# ProPrj_2026_05_15_drone_2026-05-23.net
KiCad netlist of a schematic drawn in EasyEDA Pro
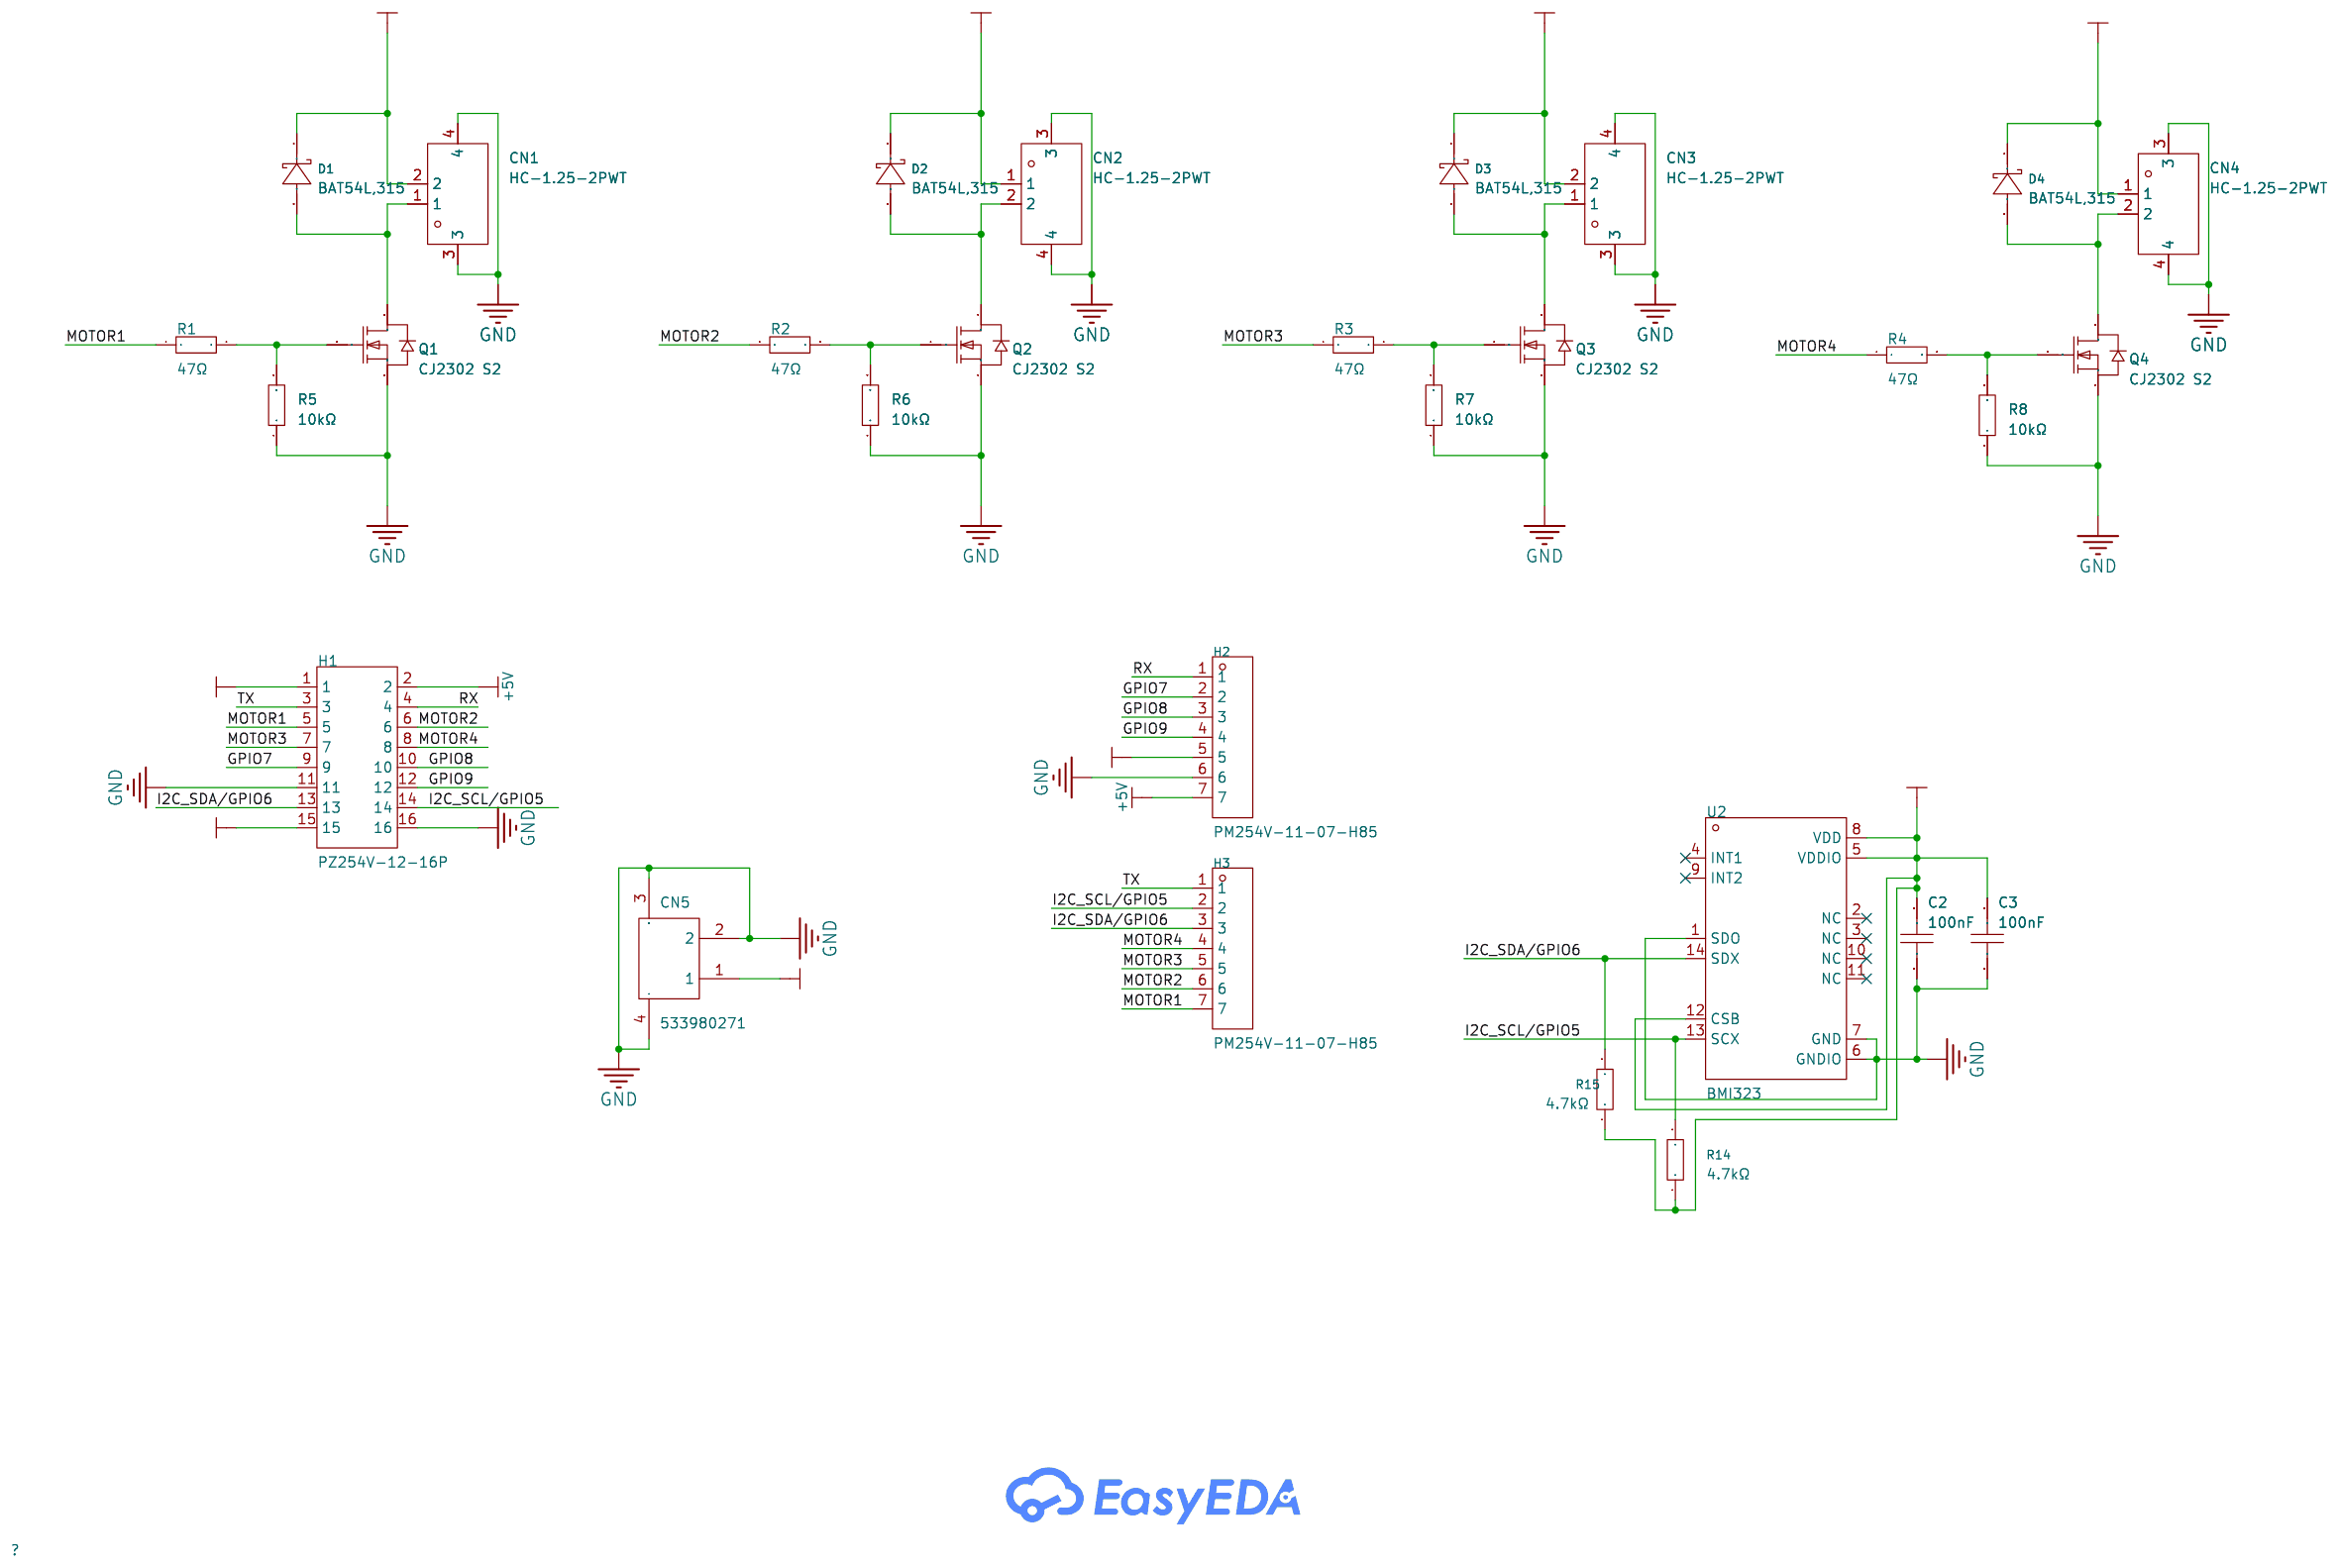
[diagram p0: schematic sheet]

(export (version "E")
  (design (tool "Eeschema 10.0.6"))
  (components
    (comp (ref "C2")
      (value "100nF")
      (footprint "easyedapro:C0402")
      (fields
        (field (name "Manufacturer Part") "CL05B104KO5NNNC")
        (field (name "Manufacturer") "SAMSUNG(三星)")
      )
      (libsource (lib "easyedapro") (part "CL05B104KO5NNNC"))
    )
    (comp (ref "C3")
      (value "100nF")
      (footprint "easyedapro:C0402")
      (fields
        (field (name "Manufacturer Part") "CL05B104KO5NNNC")
        (field (name "Manufacturer") "SAMSUNG(三星)")
      )
      (libsource (lib "easyedapro") (part "CL05B104KO5NNNC"))
    )
    (comp (ref "CN1")
      (value "HC-1.25-2PWT")
      (footprint "easyedapro:CONN-SMD_2P-P1.25-HC-1.25-2PWT")
      (fields (field (name "Manufacturer") "HCTL(华灿天禄)"))
      (libsource (lib "easyedapro") (part "HC-1.25-2PWT"))
    )
    (comp (ref "CN2")
      (value "HC-1.25-2PWT")
      (footprint "easyedapro:CONN-SMD_2P-P1.25-HC-1.25-2PWT")
      (fields (field (name "Manufacturer") "HCTL(华灿天禄)"))
      (libsource (lib "easyedapro") (part "HC-1.25-2PWT"))
    )
    (comp (ref "CN3")
      (value "HC-1.25-2PWT")
      (footprint "easyedapro:CONN-SMD_2P-P1.25-HC-1.25-2PWT")
      (fields (field (name "Manufacturer") "HCTL(华灿天禄)"))
      (libsource (lib "easyedapro") (part "HC-1.25-2PWT"))
    )
    (comp (ref "CN4")
      (value "HC-1.25-2PWT")
      (footprint "easyedapro:CONN-SMD_2P-P1.25-HC-1.25-2PWT")
      (fields (field (name "Manufacturer") "HCTL(华灿天禄)"))
      (libsource (lib "easyedapro") (part "HC-1.25-2PWT"))
    )
    (comp (ref "CN5")
      (value "533980271")
      (footprint "easyedapro:CONN-SMD_2P-P1.25_053398-0X71")
      (fields (field (name "Manufacturer") "MOLEX"))
      (libsource (lib "easyedapro") (part "0533980271"))
    )
    (comp (ref "D1")
      (value "BAT54L,315")
      (footprint "easyedapro:DFN1006-2L-RD")
      (fields (field (name "Manufacturer") "Nexperia(安世)"))
      (libsource (lib "easyedapro") (part "BAT54L,315"))
    )
    (comp (ref "D2")
      (value "BAT54L,315")
      (footprint "easyedapro:DFN1006-2L-RD")
      (fields (field (name "Manufacturer") "Nexperia(安世)"))
      (libsource (lib "easyedapro") (part "BAT54L,315"))
    )
    (comp (ref "D3")
      (value "BAT54L,315")
      (footprint "easyedapro:DFN1006-2L-RD")
      (fields (field (name "Manufacturer") "Nexperia(安世)"))
      (libsource (lib "easyedapro") (part "BAT54L,315"))
    )
    (comp (ref "D4")
      (value "BAT54L,315")
      (footprint "easyedapro:DFN1006-2L-RD")
      (fields (field (name "Manufacturer") "Nexperia(安世)"))
      (libsource (lib "easyedapro") (part "BAT54L,315"))
    )
    (comp (ref "H1")
      (value "PZ254V-12-16P")
      (footprint "easyedapro:HDR-TH_16P-P2.54-V-M-R2-C8-S2.54")
      (fields (field (name "Manufacturer") "XFCN(兴飞)"))
      (libsource (lib "easyedapro") (part "PZ254V-12-16P"))
    )
    (comp (ref "H2")
      (value "PM254V-11-07-H85")
      (footprint "easyedapro:HDR-TH_7P-P2.54-V-F")
      (fields (field (name "Manufacturer") "XFCN(兴飞)"))
      (libsource (lib "easyedapro") (part "PM254V-11-07-H85"))
    )
    (comp (ref "H3")
      (value "PM254V-11-07-H85")
      (footprint "easyedapro:HDR-TH_7P-P2.54-V-F")
      (fields (field (name "Manufacturer") "XFCN(兴飞)"))
      (libsource (lib "easyedapro") (part "PM254V-11-07-H85"))
    )
    (comp (ref "Q1")
      (value "CJ2302 S2")
      (footprint "easyedapro:SOT-23-3_L3.0-W1.7-P0.95-LS2.9-BR")
      (fields (field (name "Manufacturer") "CJ(江苏长电/长晶)"))
      (libsource (lib "easyedapro") (part "CJ2302 S2"))
    )
    (comp (ref "Q2")
      (value "CJ2302 S2")
      (footprint "easyedapro:SOT-23-3_L3.0-W1.7-P0.95-LS2.9-BR")
      (fields (field (name "Manufacturer") "CJ(江苏长电/长晶)"))
      (libsource (lib "easyedapro") (part "CJ2302 S2"))
    )
    (comp (ref "Q3")
      (value "CJ2302 S2")
      (footprint "easyedapro:SOT-23-3_L3.0-W1.7-P0.95-LS2.9-BR")
      (fields (field (name "Manufacturer") "CJ(江苏长电/长晶)"))
      (libsource (lib "easyedapro") (part "CJ2302 S2"))
    )
    (comp (ref "Q4")
      (value "CJ2302 S2")
      (footprint "easyedapro:SOT-23-3_L3.0-W1.7-P0.95-LS2.9-BR")
      (fields (field (name "Manufacturer") "CJ(江苏长电/长晶)"))
      (libsource (lib "easyedapro") (part "CJ2302 S2"))
    )
    (comp (ref "R1")
      (value "47Ω")
      (footprint "easyedapro:R0402")
      (fields (field (name "Manufacturer Part") "RC0402FR-0747RL") (field (name "Manufacturer") "YAGEO(国巨)"))
      (libsource (lib "easyedapro") (part "RC0402FR-0747RL"))
    )
    (comp (ref "R2")
      (value "47Ω")
      (footprint "easyedapro:R0402")
      (fields (field (name "Manufacturer Part") "RC0402FR-0747RL") (field (name "Manufacturer") "YAGEO(国巨)"))
      (libsource (lib "easyedapro") (part "RC0402FR-0747RL"))
    )
    (comp (ref "R3")
      (value "47Ω")
      (footprint "easyedapro:R0402")
      (fields (field (name "Manufacturer Part") "RC0402FR-0747RL") (field (name "Manufacturer") "YAGEO(国巨)"))
      (libsource (lib "easyedapro") (part "RC0402FR-0747RL"))
    )
    (comp (ref "R4")
      (value "47Ω")
      (footprint "easyedapro:R0402")
      (fields (field (name "Manufacturer Part") "RC0402FR-0747RL") (field (name "Manufacturer") "YAGEO(国巨)"))
      (libsource (lib "easyedapro") (part "RC0402FR-0747RL"))
    )
    (comp (ref "R5")
      (value "10kΩ")
      (footprint "easyedapro:R0402")
      (fields (field (name "Manufacturer Part") "RC0402FR-0710KL") (field (name "Manufacturer") "YAGEO(国巨)"))
      (libsource (lib "easyedapro") (part "RC0402FR-0710KL"))
    )
    (comp (ref "R6")
      (value "10kΩ")
      (footprint "easyedapro:R0402")
      (fields (field (name "Manufacturer Part") "RC0402FR-0710KL") (field (name "Manufacturer") "YAGEO(国巨)"))
      (libsource (lib "easyedapro") (part "RC0402FR-0710KL"))
    )
    (comp (ref "R7")
      (value "10kΩ")
      (footprint "easyedapro:R0402")
      (fields (field (name "Manufacturer Part") "RC0402FR-0710KL") (field (name "Manufacturer") "YAGEO(国巨)"))
      (libsource (lib "easyedapro") (part "RC0402FR-0710KL"))
    )
    (comp (ref "R8")
      (value "10kΩ")
      (footprint "easyedapro:R0402")
      (fields (field (name "Manufacturer Part") "RC0402FR-0710KL") (field (name "Manufacturer") "YAGEO(国巨)"))
      (libsource (lib "easyedapro") (part "RC0402FR-0710KL"))
    )
    (comp (ref "R14")
      (value "4.7kΩ")
      (footprint "easyedapro:R0402")
      (fields
        (field (name "Manufacturer Part") "0402WGF4701TCE")
        (field (name "Manufacturer") "UNI-ROYAL(厚声)")
      )
      (libsource (lib "easyedapro") (part "0402WGF4701TCE"))
    )
    (comp (ref "R15")
      (value "4.7kΩ")
      (footprint "easyedapro:R0402")
      (fields
        (field (name "Manufacturer Part") "0402WGF4701TCE")
        (field (name "Manufacturer") "UNI-ROYAL(厚声)")
      )
      (libsource (lib "easyedapro") (part "0402WGF4701TCE"))
    )
    (comp (ref "U2")
      (value "BMI323")
      (footprint "easyedapro:LGA-14_L3.0-W2.5-P0.50-TL_QMI8658A")
      (fields (field (name "Manufacturer") "Bosch(博世)"))
      (libsource (lib "easyedapro") (part "BMI323"))
    )
  )
  (nets
    (net (code "1") (name "+5V") (class "Default")
      (node (ref "H1") (pin "2") (pinfunction "2_2") (pintype "unspecified"))
      (node (ref "H2") (pin "7") (pinfunction "7_7") (pintype "input"))
    )
    (net (code "2") (name "/GPIO7") (class "Default")
      (node (ref "H1") (pin "9") (pinfunction "9_9") (pintype "unspecified"))
      (node (ref "H2") (pin "2") (pinfunction "2_2") (pintype "input"))
    )
    (net (code "3") (name "/GPIO8") (class "Default")
      (node (ref "H1") (pin "10") (pinfunction "10_10") (pintype "unspecified"))
      (node (ref "H2") (pin "3") (pinfunction "3_3") (pintype "input"))
    )
    (net (code "4") (name "/GPIO9") (class "Default")
      (node (ref "H1") (pin "12") (pinfunction "12_12") (pintype "unspecified"))
      (node (ref "H2") (pin "4") (pinfunction "4_4") (pintype "input"))
    )
    (net (code "5") (name "/I2C_SCL{slash}GPIO5") (class "Default")
      (node (ref "H1") (pin "14") (pinfunction "14_14") (pintype "unspecified"))
      (node (ref "H3") (pin "2") (pinfunction "2_2") (pintype "input"))
      (node (ref "R14") (pin "2") (pinfunction "2_2") (pintype "input"))
      (node (ref "U2") (pin "13") (pinfunction "SCX_13") (pintype "unspecified"))
    )
    (net (code "6") (name "/I2C_SDA{slash}GPIO6") (class "Default")
      (node (ref "H1") (pin "13") (pinfunction "13_13") (pintype "unspecified"))
      (node (ref "H3") (pin "3") (pinfunction "3_3") (pintype "input"))
      (node (ref "R15") (pin "2") (pinfunction "2_2") (pintype "input"))
      (node (ref "U2") (pin "14") (pinfunction "SDX_14") (pintype "unspecified"))
    )
    (net (code "7") (name "/MOTOR1") (class "Default")
      (node (ref "H1") (pin "5") (pinfunction "5_5") (pintype "unspecified"))
      (node (ref "H3") (pin "7") (pinfunction "7_7") (pintype "input"))
      (node (ref "R1") (pin "1") (pinfunction "1_1") (pintype "input"))
    )
    (net (code "8") (name "/MOTOR2") (class "Default")
      (node (ref "H1") (pin "6") (pinfunction "6_6") (pintype "unspecified"))
      (node (ref "H3") (pin "6") (pinfunction "6_6") (pintype "input"))
      (node (ref "R2") (pin "1") (pinfunction "1_1") (pintype "input"))
    )
    (net (code "9") (name "/MOTOR3") (class "Default")
      (node (ref "H1") (pin "7") (pinfunction "7_7") (pintype "unspecified"))
      (node (ref "H3") (pin "5") (pinfunction "5_5") (pintype "input"))
      (node (ref "R3") (pin "1") (pinfunction "1_1") (pintype "input"))
    )
    (net (code "10") (name "/MOTOR4") (class "Default")
      (node (ref "H1") (pin "8") (pinfunction "8_8") (pintype "unspecified"))
      (node (ref "H3") (pin "4") (pinfunction "4_4") (pintype "input"))
      (node (ref "R4") (pin "1") (pinfunction "1_1") (pintype "input"))
    )
    (net (code "11") (name "/RX") (class "Default")
      (node (ref "H1") (pin "4") (pinfunction "4_4") (pintype "unspecified"))
      (node (ref "H2") (pin "1") (pinfunction "1_1") (pintype "input"))
    )
    (net (code "12") (name "/TX") (class "Default")
      (node (ref "H1") (pin "3") (pinfunction "3_3") (pintype "unspecified"))
      (node (ref "H3") (pin "1") (pinfunction "1_1") (pintype "input"))
    )
    (net (code "13") (name "3V3") (class "Default")
      (node (ref "C2") (pin "2") (pinfunction "2_2") (pintype "unspecified"))
      (node (ref "C3") (pin "2") (pinfunction "2_2") (pintype "unspecified"))
      (node (ref "H1") (pin "15") (pinfunction "15_15") (pintype "unspecified"))
      (node (ref "H2") (pin "5") (pinfunction "5_5") (pintype "input"))
      (node (ref "R14") (pin "1") (pinfunction "1_1") (pintype "input"))
      (node (ref "R15") (pin "1") (pinfunction "1_1") (pintype "input"))
      (node (ref "U2") (pin "12") (pinfunction "CSB_12") (pintype "unspecified"))
      (node (ref "U2") (pin "5") (pinfunction "VDDIO_5") (pintype "unspecified"))
      (node (ref "U2") (pin "8") (pinfunction "VDD_8") (pintype "unspecified"))
    )
    (net (code "14") (name "GND") (class "Default")
      (node (ref "C2") (pin "1") (pinfunction "1_1") (pintype "unspecified"))
      (node (ref "C3") (pin "1") (pinfunction "1_1") (pintype "unspecified"))
      (node (ref "CN1") (pin "3") (pinfunction "3_3") (pintype "unspecified"))
      (node (ref "CN1") (pin "4") (pinfunction "4_4") (pintype "unspecified"))
      (node (ref "CN2") (pin "3") (pinfunction "3_3") (pintype "unspecified"))
      (node (ref "CN2") (pin "4") (pinfunction "4_4") (pintype "unspecified"))
      (node (ref "CN3") (pin "3") (pinfunction "3_3") (pintype "unspecified"))
      (node (ref "CN3") (pin "4") (pinfunction "4_4") (pintype "unspecified"))
      (node (ref "CN4") (pin "3") (pinfunction "3_3") (pintype "unspecified"))
      (node (ref "CN4") (pin "4") (pinfunction "4_4") (pintype "unspecified"))
      (node (ref "CN5") (pin "2") (pinfunction "2_2") (pintype "unspecified"))
      (node (ref "CN5") (pin "3") (pinfunction "3_3") (pintype "unspecified"))
      (node (ref "CN5") (pin "4") (pinfunction "4_4") (pintype "unspecified"))
      (node (ref "H1") (pin "11") (pinfunction "11_11") (pintype "unspecified"))
      (node (ref "H1") (pin "16") (pinfunction "16_16") (pintype "unspecified"))
      (node (ref "H2") (pin "6") (pinfunction "6_6") (pintype "input"))
      (node (ref "Q1") (pin "2") (pinfunction "S_2") (pintype "unspecified"))
      (node (ref "Q2") (pin "2") (pinfunction "S_2") (pintype "unspecified"))
      (node (ref "Q3") (pin "2") (pinfunction "S_2") (pintype "unspecified"))
      (node (ref "Q4") (pin "2") (pinfunction "S_2") (pintype "unspecified"))
      (node (ref "R5") (pin "1") (pinfunction "1_1") (pintype "input"))
      (node (ref "R6") (pin "1") (pinfunction "1_1") (pintype "input"))
      (node (ref "R7") (pin "1") (pinfunction "1_1") (pintype "input"))
      (node (ref "R8") (pin "1") (pinfunction "1_1") (pintype "input"))
      (node (ref "U2") (pin "1") (pinfunction "SDO_1") (pintype "unspecified"))
      (node (ref "U2") (pin "6") (pinfunction "GNDIO_6") (pintype "unspecified"))
      (node (ref "U2") (pin "7") (pinfunction "GND_7") (pintype "unspecified"))
    )
    (net (code "15") (name "Net-(D1-A)") (class "Default")
      (node (ref "CN1") (pin "1") (pinfunction "1_1") (pintype "unspecified"))
      (node (ref "D1") (pin "2") (pinfunction "A_2") (pintype "input"))
      (node (ref "Q1") (pin "3") (pinfunction "D_3") (pintype "unspecified"))
    )
    (net (code "16") (name "Net-(D2-A)") (class "Default")
      (node (ref "CN2") (pin "2") (pinfunction "2_2") (pintype "unspecified"))
      (node (ref "D2") (pin "2") (pinfunction "A_2") (pintype "input"))
      (node (ref "Q2") (pin "3") (pinfunction "D_3") (pintype "unspecified"))
    )
    (net (code "17") (name "Net-(D3-A)") (class "Default")
      (node (ref "CN3") (pin "1") (pinfunction "1_1") (pintype "unspecified"))
      (node (ref "D3") (pin "2") (pinfunction "A_2") (pintype "input"))
      (node (ref "Q3") (pin "3") (pinfunction "D_3") (pintype "unspecified"))
    )
    (net (code "18") (name "Net-(D4-A)") (class "Default")
      (node (ref "CN4") (pin "2") (pinfunction "2_2") (pintype "unspecified"))
      (node (ref "D4") (pin "2") (pinfunction "A_2") (pintype "input"))
      (node (ref "Q4") (pin "3") (pinfunction "D_3") (pintype "unspecified"))
    )
    (net (code "19") (name "Net-(Q1-G)") (class "Default")
      (node (ref "Q1") (pin "1") (pinfunction "G_1") (pintype "unspecified"))
      (node (ref "R1") (pin "2") (pinfunction "2_2") (pintype "input"))
      (node (ref "R5") (pin "2") (pinfunction "2_2") (pintype "input"))
    )
    (net (code "20") (name "Net-(Q2-G)") (class "Default")
      (node (ref "Q2") (pin "1") (pinfunction "G_1") (pintype "unspecified"))
      (node (ref "R2") (pin "2") (pinfunction "2_2") (pintype "input"))
      (node (ref "R6") (pin "2") (pinfunction "2_2") (pintype "input"))
    )
    (net (code "21") (name "Net-(Q3-G)") (class "Default")
      (node (ref "Q3") (pin "1") (pinfunction "G_1") (pintype "unspecified"))
      (node (ref "R3") (pin "2") (pinfunction "2_2") (pintype "input"))
      (node (ref "R7") (pin "2") (pinfunction "2_2") (pintype "input"))
    )
    (net (code "22") (name "Net-(Q4-G)") (class "Default")
      (node (ref "Q4") (pin "1") (pinfunction "G_1") (pintype "unspecified"))
      (node (ref "R4") (pin "2") (pinfunction "2_2") (pintype "input"))
      (node (ref "R8") (pin "2") (pinfunction "2_2") (pintype "input"))
    )
    (net (code "23") (name "VBAT") (class "Default")
      (node (ref "CN1") (pin "2") (pinfunction "2_2") (pintype "unspecified"))
      (node (ref "CN2") (pin "1") (pinfunction "1_1") (pintype "unspecified"))
      (node (ref "CN3") (pin "2") (pinfunction "2_2") (pintype "unspecified"))
      (node (ref "CN4") (pin "1") (pinfunction "1_1") (pintype "unspecified"))
      (node (ref "CN5") (pin "1") (pinfunction "1_1") (pintype "unspecified"))
      (node (ref "D1") (pin "1") (pinfunction "K_1") (pintype "input"))
      (node (ref "D2") (pin "1") (pinfunction "K_1") (pintype "input"))
      (node (ref "D3") (pin "1") (pinfunction "K_1") (pintype "input"))
      (node (ref "D4") (pin "1") (pinfunction "K_1") (pintype "input"))
      (node (ref "H1") (pin "1") (pinfunction "1_1") (pintype "unspecified"))
    )
    (net (code "24") (name "unconnected-(U2-INT1-Pad4)") (class "Default")
      (node (ref "U2") (pin "4") (pinfunction "INT1_4") (pintype "unspecified+no_connect"))
    )
    (net (code "25") (name "unconnected-(U2-INT2-Pad9)") (class "Default")
      (node (ref "U2") (pin "9") (pinfunction "INT2_9") (pintype "unspecified+no_connect"))
    )
    (net (code "26") (name "unconnected-(U2-NC-Pad2)") (class "Default")
      (node (ref "U2") (pin "2") (pinfunction "NC_2") (pintype "unspecified+no_connect"))
    )
    (net (code "27") (name "unconnected-(U2-NC-Pad3)") (class "Default")
      (node (ref "U2") (pin "3") (pinfunction "NC_3") (pintype "unspecified+no_connect"))
    )
    (net (code "28") (name "unconnected-(U2-NC-Pad10)") (class "Default")
      (node (ref "U2") (pin "10") (pinfunction "NC_10") (pintype "unspecified+no_connect"))
    )
    (net (code "29") (name "unconnected-(U2-NC-Pad11)") (class "Default")
      (node (ref "U2") (pin "11") (pinfunction "NC_11") (pintype "unspecified+no_connect"))
    )
  )
)
